# IO.net
KiCad netlist of a schematic drawn in Altium Designer
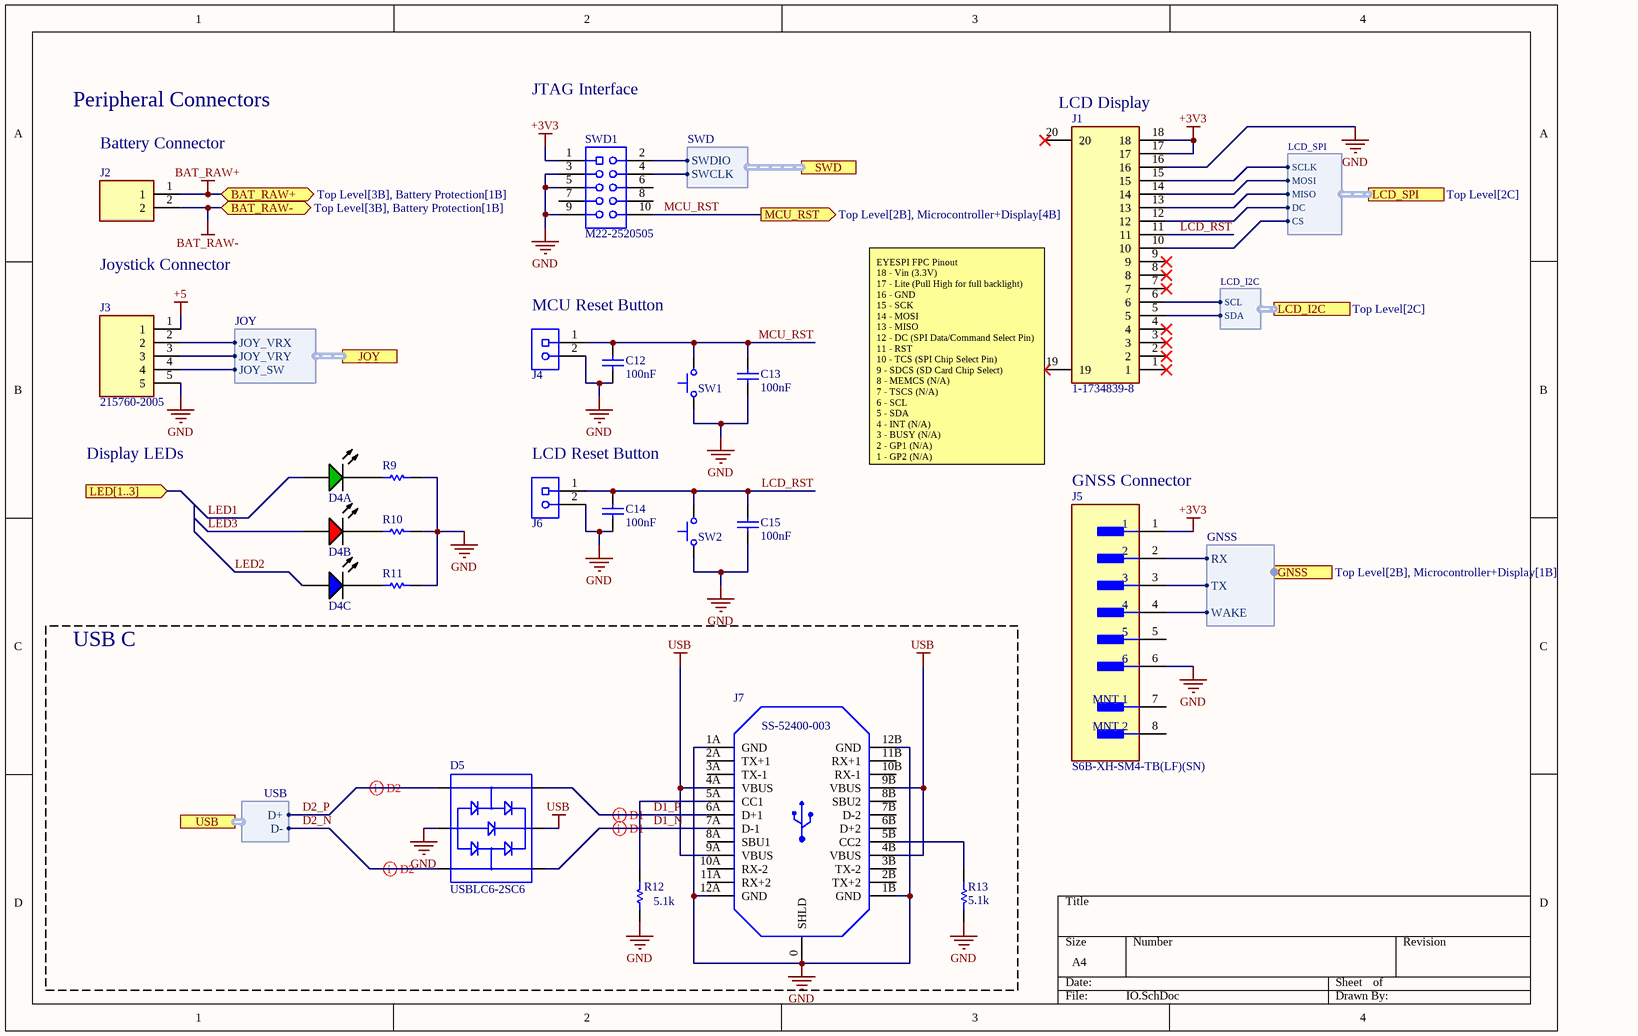
[diagram p0: IO.SchDoc]

(export (version "E")
  (design (tool "Eeschema 10.0.6"))
  (components
    (comp (ref "C12")
      (value "100nF")
      (footprint "CAPC1608X10N")
      (description "Cap Ceramic 0.1uF 50V X7R 20% SMD 0603 125C T/R")
      (fields (field (name "TOLERANCE") "20%") (field (name "Comment") "C0603C104M5RACTU"))
      (libsource (lib "Receiver_Library") (part "C0603C104M5RACTU"))
    )
    (comp (ref "C13")
      (value "100nF")
      (footprint "CAPC1608X10N")
      (description "Cap Ceramic 0.1uF 50V X7R 20% SMD 0603 125C T/R")
      (fields (field (name "TOLERANCE") "20%") (field (name "Comment") "C0603C104M5RACTU"))
      (libsource (lib "Receiver_Library") (part "C0603C104M5RACTU"))
    )
    (comp (ref "C14")
      (value "100nF")
      (footprint "CAPC1608X10N")
      (description "Cap Ceramic 0.1uF 50V X7R 20% SMD 0603 125C T/R")
      (fields (field (name "TOLERANCE") "20%") (field (name "Comment") "C0603C104M5RACTU"))
      (libsource (lib "Receiver_Library") (part "C0603C104M5RACTU"))
    )
    (comp (ref "C15")
      (value "100nF")
      (footprint "CAPC1608X10N")
      (description "Cap Ceramic 0.1uF 50V X7R 20% SMD 0603 125C T/R")
      (fields (field (name "TOLERANCE") "20%") (field (name "Comment") "C0603C104M5RACTU"))
      (libsource (lib "Receiver_Library") (part "C0603C104M5RACTU"))
    )
    (comp (ref "D4")
      (value "LRTBGVSR-U4V2-JW+A6BB-D8+S2U2-7Z-20-S")
      (footprint "LRTBGVSG-UEVE-24+AMAQ-29+SCUC-HR-Footprint-1")
      (description "LED Multicolor Red/True Green/Blue 626nm/528nm/465nm 40mA/50mA/50mA 6-Pin SMD T/R")
      (libsource (lib "Receiver_Library") (part "LRTBGVSR-U4V2-JW+A6BB-D8+S2U2-7Z-20-S"))
    )
    (comp (ref "D5")
      (value "USBLC6-2SC6")
      (footprint "USBLC6-2SC6")
      (description "ESD Suppressors / TVS Diodes ESD Protection Low Cap")
      (libsource (lib "Receiver_Library") (part "USBLC6-2SC6"))
    )
    (comp (ref "J1")
      (value "1-1734839-8")
      (footprint "117348398")
      (description "AMP - TE CONNECTIVITY - 1-1734839-8 - CONNECTOR")
      (fields (field (name "MOUSER PART NUMBER") "571-1-1734839-8"))
      (libsource (lib "Receiver_Library") (part "1-1734839-8"))
    )
    (comp (ref "J2")
      (value "S2B-PH-K-S__LF__SN_")
      (footprint "SamacSys:SHDRRA2W50P0X200_1X2_590X760X480P")
      (description "Connector")
      (fields (field (name "MANUFACTURER_PART_NUMBER") "S2B-PH-K-S (LF)(SN)"))
      (libsource (lib "*") (part "S2B-PH-K-S__LF__SN_"))
    )
    (comp (ref "J3")
      (value "215760-2005")
      (footprint "SamacSys:215760-YY05")
      (description "Connector")
      (fields (field (name "MOUSER PART NUMBER") "538-215760-2005"))
      (libsource (lib "Receiver_Library") (part "215760-2005"))
    )
    (comp (ref "J4")
      (value "22-28-4020")
      (footprint "22-28-4020")
      (description "KK 254 Breakaway Header, Vertical, 2 Circuits, Tin (Sn) Plating, Mating Pin Length 6.09mm 2 POS")
      (libsource (lib "Receiver_Library") (part "22-28-4020"))
    )
    (comp (ref "J5")
      (value "S6B-XH-SM4-TB(LF)(SN)")
      (footprint "FP-S6B-XH-SM4-TB_LF_SN-MFG")
      (description "CONN HEADER SMD R/A 6POS 2.5MM")
      (libsource (lib "Receiver_Library") (part "S6B-XH-SM4-TB(LF)(SN)"))
    )
    (comp (ref "J6")
      (value "22-28-4020")
      (footprint "22-28-4020")
      (description "KK 254 Breakaway Header, Vertical, 2 Circuits, Tin (Sn) Plating, Mating Pin Length 6.09mm 2 POS")
      (libsource (lib "Receiver_Library") (part "22-28-4020"))
    )
    (comp (ref "J7")
      (value "SS-52400-003")
      (footprint "SS52400005")
      (description "USB Type-C Receptacle for 1.60mm PCB")
      (fields
        (field (name "MANUFACTURER_PART_NUMBER") "SS-52400-005")
        (field (name "MOUSER PART NUMBER") "530-SS-52400-005")
      )
      (libsource (lib "Receiver_Library") (part "SS-52400-003"))
    )
    (comp (ref "R9")
      (value "CRCW06031K00FKEA")
      (footprint "0603")
      (libsource (lib "Receiver_Library") (part "CRCW06031K00FKEA"))
    )
    (comp (ref "R10")
      (value "CRCW06031K00FKEA")
      (footprint "0603")
      (libsource (lib "Receiver_Library") (part "CRCW06031K00FKEA"))
    )
    (comp (ref "R11")
      (value "CRCW06031K00FKEA")
      (footprint "0603")
      (libsource (lib "Receiver_Library") (part "CRCW06031K00FKEA"))
    )
    (comp (ref "R12")
      (value "5.1k")
      (footprint "0603")
      (description "Res Thick Film 0603 5.1K Ohm 1% 1/10W ±100ppm/°C Molded SMD SMD Paper T/R")
      (fields (field (name "Comment") "CRCW06035K10FKEA"))
      (libsource (lib "Receiver_Library") (part "CRCW06035K10FKEA"))
    )
    (comp (ref "R13")
      (value "5.1k")
      (footprint "0603")
      (description "Res Thick Film 0603 5.1K Ohm 1% 1/10W ±100ppm/°C Molded SMD SMD Paper T/R")
      (fields (field (name "Comment") "CRCW06035K10FKEA"))
      (libsource (lib "Receiver_Library") (part "CRCW06035K10FKEA"))
    )
    (comp (ref "SW1")
      (value "B3U-1000P")
      (footprint "B3U-1000P")
      (description "SWITCH TACTILE SPST-NO 0.05A 12V")
      (libsource (lib "Receiver_Library") (part "B3U-1000P"))
    )
    (comp (ref "SW2")
      (value "B3U-1000P")
      (footprint "B3U-1000P")
      (description "SWITCH TACTILE SPST-NO 0.05A 12V")
      (libsource (lib "Receiver_Library") (part "B3U-1000P"))
    )
    (comp (ref "SWD1")
      (value "M22-2520505")
      (footprint "M22-2520505")
      (libsource (lib "Receiver_Library") (part "M22-2520505"))
    )
  )
  (nets
    (net (code "6") (name "+3V3") (class "Default")
      (node (ref "J1") (pin "17") (pinfunction "17_17") (pintype "passive"))
      (node (ref "J1") (pin "18") (pinfunction "18_18") (pintype "passive"))
      (node (ref "J5") (pin "1") (pinfunction "1_1") (pintype "passive"))
      (node (ref "SWD1") (pin "1") (pinfunction "VDD_1") (pintype "passive"))
    )
    (net (code "7") (name "+5") (class "Default")
      (node (ref "J3") (pin "1") (pinfunction "1_1") (pintype "passive"))
    )
    (net (code "8") (name "/CS") (class "Default")
      (node (ref "J1") (pin "10") (pinfunction "10_10") (pintype "passive"))
    )
    (net (code "9") (name "/D1_N") (class "Default")
      (node (ref "D5") (pin "6") (pinfunction "6_6") (pintype "passive"))
      (node (ref "J7") (pin "7A") (pinfunction "D-1_7A") (pintype "passive"))
    )
    (net (code "10") (name "/D1_P") (class "Default")
      (node (ref "D5") (pin "4") (pinfunction "4_4") (pintype "passive"))
      (node (ref "J7") (pin "6A") (pinfunction "D+1_6A") (pintype "passive"))
    )
    (net (code "11") (name "/D2_N") (class "Default")
      (node (ref "D5") (pin "1") (pinfunction "1_1") (pintype "passive"))
    )
    (net (code "12") (name "/D2_P") (class "Default")
      (node (ref "D5") (pin "3") (pinfunction "3_3") (pintype "passive"))
    )
    (net (code "13") (name "/DC") (class "Default")
      (node (ref "J1") (pin "12") (pinfunction "12_12") (pintype "passive"))
    )
    (net (code "14") (name "/JOY_SW") (class "Default")
      (node (ref "J3") (pin "4") (pinfunction "4_4") (pintype "passive"))
    )
    (net (code "15") (name "/JOY_VRX") (class "Default")
      (node (ref "J3") (pin "2") (pinfunction "2_2") (pintype "passive"))
    )
    (net (code "16") (name "/JOY_VRY") (class "Default")
      (node (ref "J3") (pin "3") (pinfunction "3_3") (pintype "passive"))
    )
    (net (code "17") (name "/LCD_RST") (class "Default")
      (node (ref "C14") (pin "2") (pinfunction "2_2") (pintype "passive"))
      (node (ref "C15") (pin "2") (pinfunction "2_2") (pintype "passive"))
      (node (ref "J1") (pin "11") (pinfunction "11_11") (pintype "passive"))
      (node (ref "J6") (pin "1") (pinfunction "1_1") (pintype "passive"))
      (node (ref "SW2") (pin "2") (pinfunction "2_2") (pintype "passive"))
    )
    (net (code "18") (name "/LED1") (class "Default")
      (node (ref "D4") (pin "6") (pinfunction "A1_6") (pintype "passive"))
    )
    (net (code "19") (name "/LED2") (class "Default")
      (node (ref "D4") (pin "2") (pinfunction "A3_2") (pintype "passive"))
    )
    (net (code "20") (name "/LED3") (class "Default")
      (node (ref "D4") (pin "5") (pinfunction "A2_5") (pintype "passive"))
    )
    (net (code "22") (name "/MCU_RST") (class "Default")
      (node (ref "C12") (pin "2") (pinfunction "2_2") (pintype "passive"))
      (node (ref "C13") (pin "2") (pinfunction "2_2") (pintype "passive"))
      (node (ref "J4") (pin "1") (pinfunction "1_1") (pintype "passive"))
      (node (ref "SW1") (pin "2") (pinfunction "2_2") (pintype "passive"))
      (node (ref "SWD1") (pin "10") (pinfunction "NRST_10") (pintype "passive"))
    )
    (net (code "23") (name "/MISO") (class "Default")
      (node (ref "J1") (pin "13") (pinfunction "13_13") (pintype "passive"))
    )
    (net (code "24") (name "/MOSI") (class "Default")
      (node (ref "J1") (pin "14") (pinfunction "14_14") (pintype "passive"))
    )
    (net (code "25") (name "/RX") (class "Default")
      (node (ref "J5") (pin "2") (pinfunction "2_2") (pintype "passive"))
    )
    (net (code "26") (name "/SCL") (class "Default")
      (node (ref "J1") (pin "6") (pinfunction "6_6") (pintype "passive"))
    )
    (net (code "27") (name "/SCLK") (class "Default")
      (node (ref "J1") (pin "15") (pinfunction "15_15") (pintype "passive"))
    )
    (net (code "28") (name "/SDA") (class "Default")
      (node (ref "J1") (pin "5") (pinfunction "5_5") (pintype "passive"))
    )
    (net (code "29") (name "/SWCLK") (class "Default")
      (node (ref "SWD1") (pin "4") (pinfunction "SWCLK_4") (pintype "passive"))
    )
    (net (code "30") (name "/SWDIO") (class "Default")
      (node (ref "SWD1") (pin "2") (pinfunction "SWDIO_2") (pintype "passive"))
    )
    (net (code "31") (name "/TX") (class "Default")
      (node (ref "J5") (pin "3") (pinfunction "3_3") (pintype "passive"))
    )
    (net (code "32") (name "/WAKE") (class "Default")
      (node (ref "J5") (pin "4") (pinfunction "4_4") (pintype "passive"))
    )
    (net (code "39") (name "BAT_RAW+") (class "Default")
      (node (ref "J2") (pin "1") (pinfunction "1_1") (pintype "passive"))
    )
    (net (code "40") (name "BAT_RAW-") (class "Default")
      (node (ref "J2") (pin "2") (pinfunction "2_2") (pintype "passive"))
    )
    (net (code "41") (name "GND") (class "Default")
      (node (ref "C12") (pin "1") (pinfunction "1_1") (pintype "passive"))
      (node (ref "C13") (pin "1") (pinfunction "1_1") (pintype "passive"))
      (node (ref "C14") (pin "1") (pinfunction "1_1") (pintype "passive"))
      (node (ref "C15") (pin "1") (pinfunction "1_1") (pintype "passive"))
      (node (ref "D5") (pin "2") (pinfunction "2_2") (pintype "passive"))
      (node (ref "J1") (pin "16") (pinfunction "16_16") (pintype "passive"))
      (node (ref "J3") (pin "5") (pinfunction "5_5") (pintype "passive"))
      (node (ref "J4") (pin "2") (pinfunction "2_2") (pintype "passive"))
      (node (ref "J5") (pin "6") (pinfunction "6_6") (pintype "passive"))
      (node (ref "J6") (pin "2") (pinfunction "2_2") (pintype "passive"))
      (node (ref "J7") (pin "0") (pinfunction "SHLD_0") (pintype "passive"))
      (node (ref "J7") (pin "12A") (pinfunction "GND_12A") (pintype "passive"))
      (node (ref "J7") (pin "12B") (pinfunction "GND_12B") (pintype "passive"))
      (node (ref "J7") (pin "1A") (pinfunction "GND_1A") (pintype "passive"))
      (node (ref "J7") (pin "1B") (pinfunction "GND_1B") (pintype "passive"))
      (node (ref "R10") (pin "2") (pinfunction "2_2") (pintype "passive"))
      (node (ref "R11") (pin "2") (pinfunction "2_2") (pintype "passive"))
      (node (ref "R12") (pin "1") (pinfunction "1_1") (pintype "passive"))
      (node (ref "R13") (pin "1") (pinfunction "1_1") (pintype "passive"))
      (node (ref "R9") (pin "2") (pinfunction "2_2") (pintype "passive"))
      (node (ref "SW1") (pin "1") (pinfunction "1_1") (pintype "passive"))
      (node (ref "SW2") (pin "1") (pinfunction "1_1") (pintype "passive"))
      (node (ref "SWD1") (pin "3") (pinfunction "GND_3") (pintype "passive"))
      (node (ref "SWD1") (pin "5") (pinfunction "GND_5") (pintype "passive"))
      (node (ref "SWD1") (pin "9") (pinfunction "GND_9") (pintype "passive"))
    )
    (net (code "42") (name "Net-(D4A-K1)") (class "Default")
      (node (ref "D4") (pin "1") (pinfunction "K1_1") (pintype "passive"))
      (node (ref "R9") (pin "1") (pinfunction "1_1") (pintype "passive"))
    )
    (net (code "43") (name "Net-(D4B-K2)") (class "Default")
      (node (ref "D4") (pin "4") (pinfunction "K2_4") (pintype "passive"))
      (node (ref "R10") (pin "1") (pinfunction "1_1") (pintype "passive"))
    )
    (net (code "44") (name "Net-(D4C-K3)") (class "Default")
      (node (ref "D4") (pin "3") (pinfunction "K3_3") (pintype "passive"))
      (node (ref "R11") (pin "1") (pinfunction "1_1") (pintype "passive"))
    )
    (net (code "45") (name "Net-(J7-CC1)") (class "Default")
      (node (ref "J7") (pin "5A") (pinfunction "CC1_5A") (pintype "passive"))
      (node (ref "R12") (pin "2") (pinfunction "2_2") (pintype "passive"))
    )
    (net (code "46") (name "Net-(J7-CC2)") (class "Default")
      (node (ref "J7") (pin "5B") (pinfunction "CC2_5B") (pintype "passive"))
      (node (ref "R13") (pin "2") (pinfunction "2_2") (pintype "passive"))
    )
    (net (code "47") (name "USB") (class "Default")
      (node (ref "D5") (pin "5") (pinfunction "5_5") (pintype "passive"))
      (node (ref "J7") (pin "4A") (pinfunction "VBUS_4A") (pintype "passive"))
      (node (ref "J7") (pin "4B") (pinfunction "VBUS_4B") (pintype "passive"))
      (node (ref "J7") (pin "9A") (pinfunction "VBUS_9A") (pintype "passive"))
      (node (ref "J7") (pin "9B") (pinfunction "VBUS_9B") (pintype "passive"))
    )
    (net (code "48") (name "unconnected-(J1-Pad1)") (class "Default")
      (node (ref "J1") (pin "1") (pinfunction "1_1") (pintype "passive+no_connect"))
    )
    (net (code "49") (name "unconnected-(J1-Pad2)") (class "Default")
      (node (ref "J1") (pin "2") (pinfunction "2_2") (pintype "passive+no_connect"))
    )
    (net (code "50") (name "unconnected-(J1-Pad3)") (class "Default")
      (node (ref "J1") (pin "3") (pinfunction "3_3") (pintype "passive+no_connect"))
    )
    (net (code "51") (name "unconnected-(J1-Pad4)") (class "Default")
      (node (ref "J1") (pin "4") (pinfunction "4_4") (pintype "passive+no_connect"))
    )
    (net (code "52") (name "unconnected-(J1-Pad7)") (class "Default")
      (node (ref "J1") (pin "7") (pinfunction "7_7") (pintype "passive+no_connect"))
    )
    (net (code "53") (name "unconnected-(J1-Pad8)") (class "Default")
      (node (ref "J1") (pin "8") (pinfunction "8_8") (pintype "passive+no_connect"))
    )
    (net (code "54") (name "unconnected-(J1-Pad9)") (class "Default")
      (node (ref "J1") (pin "9") (pinfunction "9_9") (pintype "passive+no_connect"))
    )
    (net (code "55") (name "unconnected-(J1-Pad19)") (class "Default")
      (node (ref "J1") (pin "19") (pinfunction "19_19") (pintype "passive+no_connect"))
    )
    (net (code "56") (name "unconnected-(J1-Pad20)") (class "Default")
      (node (ref "J1") (pin "20") (pinfunction "20_20") (pintype "passive+no_connect"))
    )
    (net (code "57") (name "unconnected-(J5-MNT_1-Pad7)") (class "Default")
      (node (ref "J5") (pin "7") (pinfunction "MNT_1_7") (pintype "passive"))
    )
    (net (code "58") (name "unconnected-(J5-MNT_2-Pad8)") (class "Default")
      (node (ref "J5") (pin "8") (pinfunction "MNT_2_8") (pintype "passive"))
    )
    (net (code "59") (name "unconnected-(J5-Pad5)") (class "Default")
      (node (ref "J5") (pin "5") (pinfunction "5_5") (pintype "passive"))
    )
    (net (code "60") (name "unconnected-(J7-D+2-Pad6B)") (class "Default")
      (node (ref "J7") (pin "6B") (pinfunction "D+2_6B") (pintype "passive"))
    )
    (net (code "61") (name "unconnected-(J7-D-2-Pad7B)") (class "Default")
      (node (ref "J7") (pin "7B") (pinfunction "D-2_7B") (pintype "passive"))
    )
    (net (code "62") (name "unconnected-(J7-RX+1-Pad11B)") (class "Default")
      (node (ref "J7") (pin "11B") (pinfunction "RX+1_11B") (pintype "passive"))
    )
    (net (code "63") (name "unconnected-(J7-RX+2-Pad11A)") (class "Default")
      (node (ref "J7") (pin "11A") (pinfunction "RX+2_11A") (pintype "passive"))
    )
    (net (code "64") (name "unconnected-(J7-RX-1-Pad10B)") (class "Default")
      (node (ref "J7") (pin "10B") (pinfunction "RX-1_10B") (pintype "passive"))
    )
    (net (code "65") (name "unconnected-(J7-RX-2-Pad10A)") (class "Default")
      (node (ref "J7") (pin "10A") (pinfunction "RX-2_10A") (pintype "passive"))
    )
    (net (code "66") (name "unconnected-(J7-SBU1-Pad8A)") (class "Default")
      (node (ref "J7") (pin "8A") (pinfunction "SBU1_8A") (pintype "passive"))
    )
    (net (code "67") (name "unconnected-(J7-SBU2-Pad8B)") (class "Default")
      (node (ref "J7") (pin "8B") (pinfunction "SBU2_8B") (pintype "passive"))
    )
    (net (code "68") (name "unconnected-(J7-TX+1-Pad2A)") (class "Default")
      (node (ref "J7") (pin "2A") (pinfunction "TX+1_2A") (pintype "passive"))
    )
    (net (code "69") (name "unconnected-(J7-TX+2-Pad2B)") (class "Default")
      (node (ref "J7") (pin "2B") (pinfunction "TX+2_2B") (pintype "passive"))
    )
    (net (code "70") (name "unconnected-(J7-TX-1-Pad3A)") (class "Default")
      (node (ref "J7") (pin "3A") (pinfunction "TX-1_3A") (pintype "passive"))
    )
    (net (code "71") (name "unconnected-(J7-TX-2-Pad3B)") (class "Default")
      (node (ref "J7") (pin "3B") (pinfunction "TX-2_3B") (pintype "passive"))
    )
    (net (code "72") (name "unconnected-(SWD1-NC-Pad7)") (class "Default")
      (node (ref "SWD1") (pin "7") (pinfunction "NC_7") (pintype "passive"))
    )
    (net (code "73") (name "unconnected-(SWD1-NC-Pad8)") (class "Default")
      (node (ref "SWD1") (pin "8") (pinfunction "NC_8") (pintype "passive"))
    )
    (net (code "74") (name "unconnected-(SWD1-SWO-Pad6)") (class "Default")
      (node (ref "SWD1") (pin "6") (pinfunction "SWO_6") (pintype "passive"))
    )
  )
)
